# gps.net
KiCad netlist of a schematic drawn in Altium Designer
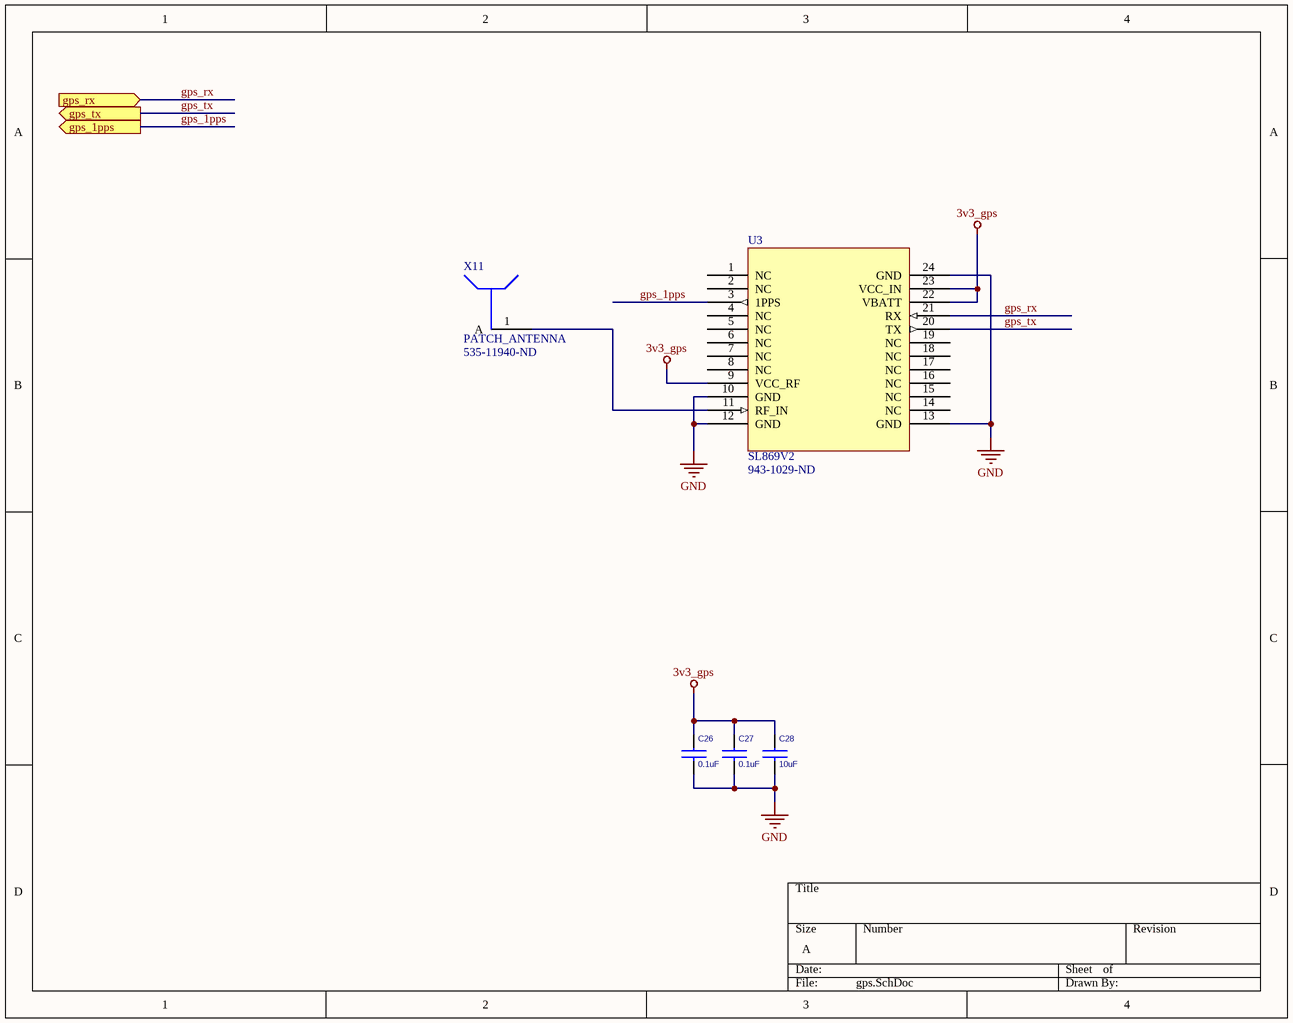
[diagram p0: gps.SchDoc]

(export (version "E")
  (design (tool "Eeschema 10.0.6"))
  (components
    (comp (ref "C26")
      (value "0.1uF")
      (footprint "CAPC2012X09M")
      (description "CAP CER 0.1UF 25V 10% X7R 0805")
      (libsource (lib "Capacitors") (part "CAP_SMD_0.1UF_10%"))
    )
    (comp (ref "C27")
      (value "0.1uF")
      (footprint "CAPC2012X09M")
      (description "CAP CER 0.1UF 25V 10% X7R 0805")
      (libsource (lib "Capacitors") (part "CAP_SMD_0.1UF_10%"))
    )
    (comp (ref "C28")
      (value "10uF")
      (footprint "CAPC2012X09M")
      (description "CAP CER 10UF 16V 20% X5R 0805")
      (libsource (lib "Capacitors") (part "CAP_SMD_10UF_20%"))
    )
    (comp (ref "U3")
      (value "SL869V2")
      (footprint "SL869V2_FOOT")
      (fields (field (name "SUPPLIER PART NUMBER 1") "943-1029-ND"))
      (libsource (lib "TruthEar") (part "SL869V2"))
    )
    (comp (ref "X11")
      (value "PATCH_ANTENNA")
      (footprint "PATCH_ANTENNA")
      (fields (field (name "SUPPLIER PART NUMBER 1") "535-11940-ND"))
      (libsource (lib "TruthEar") (part "PATCH_ANTENNA"))
    )
  )
  (nets
    (net (code "1") (name "/gps_1pps") (class "Default")
      (node (ref "U3") (pin "3") (pinfunction "1PPS_3") (pintype "output"))
    )
    (net (code "2") (name "/gps_rx") (class "Default")
      (node (ref "U3") (pin "21") (pinfunction "RX_21") (pintype "input"))
    )
    (net (code "3") (name "/gps_tx") (class "Default")
      (node (ref "U3") (pin "20") (pinfunction "TX_20") (pintype "output"))
    )
    (net (code "4") (name "3v3_gps") (class "Default")
      (node (ref "C26") (pin "1") (pinfunction "1_1") (pintype "passive"))
      (node (ref "C27") (pin "1") (pinfunction "1_1") (pintype "passive"))
      (node (ref "C28") (pin "1") (pinfunction "1_1") (pintype "passive"))
      (node (ref "U3") (pin "22") (pinfunction "VBATT_22") (pintype "passive"))
      (node (ref "U3") (pin "23") (pinfunction "VCC_IN_23") (pintype "passive"))
      (node (ref "U3") (pin "9") (pinfunction "VCC_RF_9") (pintype "passive"))
    )
    (net (code "5") (name "GND") (class "Default")
      (node (ref "C26") (pin "2") (pinfunction "2_2") (pintype "passive"))
      (node (ref "C27") (pin "2") (pinfunction "2_2") (pintype "passive"))
      (node (ref "C28") (pin "2") (pinfunction "2_2") (pintype "passive"))
      (node (ref "U3") (pin "10") (pinfunction "GND_10") (pintype "passive"))
      (node (ref "U3") (pin "12") (pinfunction "GND_12") (pintype "passive"))
      (node (ref "U3") (pin "13") (pinfunction "GND_13") (pintype "passive"))
      (node (ref "U3") (pin "24") (pinfunction "GND_24") (pintype "passive"))
    )
    (net (code "6") (name "Net-(U3-RF_IN)") (class "Default")
      (node (ref "U3") (pin "11") (pinfunction "RF_IN_11") (pintype "input"))
      (node (ref "X11") (pin "1") (pinfunction "A_1") (pintype "passive"))
    )
    (net (code "7") (name "unconnected-(U3-NC-Pad1)") (class "Default")
      (node (ref "U3") (pin "1") (pinfunction "NC_1") (pintype "passive"))
    )
    (net (code "8") (name "unconnected-(U3-NC-Pad2)") (class "Default")
      (node (ref "U3") (pin "2") (pinfunction "NC_2") (pintype "passive"))
    )
    (net (code "9") (name "unconnected-(U3-NC-Pad4)") (class "Default")
      (node (ref "U3") (pin "4") (pinfunction "NC_4") (pintype "passive"))
    )
    (net (code "10") (name "unconnected-(U3-NC-Pad5)") (class "Default")
      (node (ref "U3") (pin "5") (pinfunction "NC_5") (pintype "passive"))
    )
    (net (code "11") (name "unconnected-(U3-NC-Pad6)") (class "Default")
      (node (ref "U3") (pin "6") (pinfunction "NC_6") (pintype "passive"))
    )
    (net (code "12") (name "unconnected-(U3-NC-Pad7)") (class "Default")
      (node (ref "U3") (pin "7") (pinfunction "NC_7") (pintype "passive"))
    )
    (net (code "13") (name "unconnected-(U3-NC-Pad8)") (class "Default")
      (node (ref "U3") (pin "8") (pinfunction "NC_8") (pintype "passive"))
    )
    (net (code "14") (name "unconnected-(U3-NC-Pad14)") (class "Default")
      (node (ref "U3") (pin "14") (pinfunction "NC_14") (pintype "passive"))
    )
    (net (code "15") (name "unconnected-(U3-NC-Pad15)") (class "Default")
      (node (ref "U3") (pin "15") (pinfunction "NC_15") (pintype "passive"))
    )
    (net (code "16") (name "unconnected-(U3-NC-Pad16)") (class "Default")
      (node (ref "U3") (pin "16") (pinfunction "NC_16") (pintype "passive"))
    )
    (net (code "17") (name "unconnected-(U3-NC-Pad17)") (class "Default")
      (node (ref "U3") (pin "17") (pinfunction "NC_17") (pintype "passive"))
    )
    (net (code "18") (name "unconnected-(U3-NC-Pad18)") (class "Default")
      (node (ref "U3") (pin "18") (pinfunction "NC_18") (pintype "passive"))
    )
    (net (code "19") (name "unconnected-(U3-NC-Pad19)") (class "Default")
      (node (ref "U3") (pin "19") (pinfunction "NC_19") (pintype "passive"))
    )
  )
)
